# Sheet1.net
KiCad netlist of a schematic drawn in Altium Designer
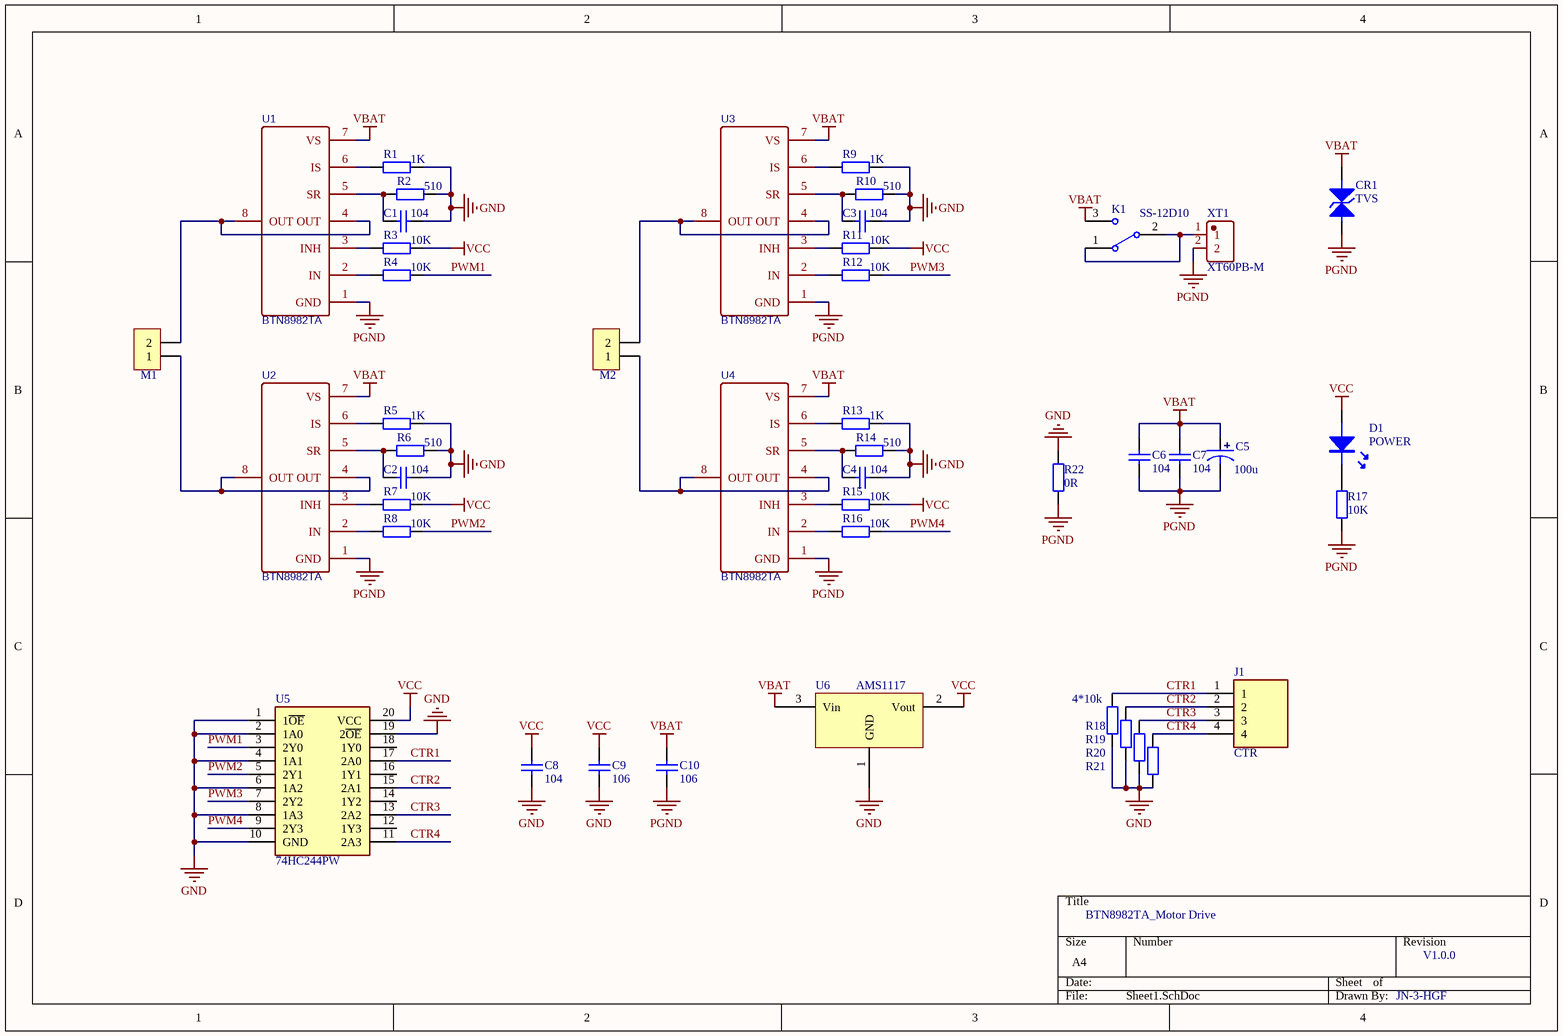
[diagram p0: Sheet1.SchDoc]

(export (version "E")
  (design (tool "Eeschema 10.0.6"))
  (components
    (comp (ref "C1")
      (value "104")
      (footprint "稽稽库:CAP0603")
      (description "Capacitor")
      (fields (field (name "Comment") "Cap") (field (name "PUBLISHER") "Altium Limited"))
      (libsource (lib "Miscellaneous Devices") (part "Cap"))
    )
    (comp (ref "C2")
      (value "104")
      (footprint "稽稽库:CAP0603")
      (description "Capacitor")
      (fields (field (name "Comment") "Cap") (field (name "PUBLISHER") "Altium Limited"))
      (libsource (lib "Miscellaneous Devices") (part "Cap"))
    )
    (comp (ref "C3")
      (value "104")
      (footprint "稽稽库:CAP0603")
      (description "Capacitor")
      (fields (field (name "Comment") "Cap") (field (name "PUBLISHER") "Altium Limited"))
      (libsource (lib "Miscellaneous Devices") (part "Cap"))
    )
    (comp (ref "C4")
      (value "104")
      (footprint "稽稽库:CAP0603")
      (description "Capacitor")
      (fields (field (name "Comment") "Cap") (field (name "PUBLISHER") "Altium Limited"))
      (libsource (lib "Miscellaneous Devices") (part "Cap"))
    )
    (comp (ref "C5")
      (value "100u")
      (footprint "SMD-EC6.3X6.3X10")
      (description "贴片电解电容")
      (libsource (lib "电容") (part "SMD_ECAP"))
    )
    (comp (ref "C6")
      (value "104")
      (footprint "稽稽库:CAP0603")
      (description "Capacitor")
      (fields (field (name "Comment") "Cap") (field (name "PUBLISHER") "Altium Limited"))
      (libsource (lib "Miscellaneous Devices") (part "Cap"))
    )
    (comp (ref "C7")
      (value "104")
      (footprint "稽稽库:CAP0603")
      (description "Capacitor")
      (fields (field (name "Comment") "Cap") (field (name "PUBLISHER") "Altium Limited"))
      (libsource (lib "Miscellaneous Devices") (part "Cap"))
    )
    (comp (ref "C8")
      (value "104")
      (footprint "稽稽库:CAP0603")
      (description "Capacitor")
      (fields (field (name "Comment") "Cap") (field (name "PUBLISHER") "Altium Limited"))
      (libsource (lib "Miscellaneous Devices") (part "Cap"))
    )
    (comp (ref "C9")
      (value "106")
      (footprint "稽稽库:CAP0603")
      (description "Capacitor")
      (fields (field (name "Comment") "Cap") (field (name "PUBLISHER") "Altium Limited"))
      (libsource (lib "Miscellaneous Devices") (part "Cap"))
    )
    (comp (ref "C10")
      (value "106")
      (footprint "稽稽库:CAP0603")
      (description "Capacitor")
      (fields (field (name "Comment") "Cap") (field (name "PUBLISHER") "Altium Limited"))
      (libsource (lib "Miscellaneous Devices") (part "Cap"))
    )
    (comp (ref "CR1")
      (value "TVS")
      (footprint "SMA/DO-214AC")
      (description "双向瞬态抑制二极管")
      (libsource (lib "二极管") (part "TVS"))
    )
    (comp (ref "D1") (value "POWER") (footprint "LED-0603G") (libsource (lib "LED") (part "LED")))
    (comp (ref "J1")
      (value "CTR")
      (footprint "XH2.54-LI-4P")
      (description "Connector")
      (fields (field (name "MANUFACTURER_PART_NUMBER") "B4B-XH-A(LF)(SN)"))
      (libsource (lib "*") (part "B4B-XH-A_LF__SN_"))
    )
    (comp (ref "K1") (value "SS-12D10") (footprint "SS-12D10") (libsource (lib "电源开关") (part "SS-12D10")))
    (comp (ref "M1")
      (value "HDR-1X2")
      (footprint "KF301-5.0-2P")
      (description "2P接插件")
      (fields (field (name "版权归属") "源创客"))
      (libsource (lib "4.10 - 接插件-脚距5.0") (part "Header 2"))
    )
    (comp (ref "M2")
      (value "HDR-1X2")
      (footprint "KF301-5.0-2P")
      (description "2P接插件")
      (fields (field (name "版权归属") "源创客"))
      (libsource (lib "4.10 - 接插件-脚距5.0") (part "Header 2"))
    )
    (comp (ref "R1")
      (value "1K")
      (footprint "稽稽库:R0603")
      (description "Resistor")
      (fields (field (name "Comment") "Res2") (field (name "PUBLISHER") "Altium Limited"))
      (libsource (lib "Miscellaneous Devices") (part "Res2"))
    )
    (comp (ref "R2")
      (value "510")
      (footprint "稽稽库:R0603")
      (description "Resistor")
      (fields (field (name "Comment") "Res2") (field (name "PUBLISHER") "Altium Limited"))
      (libsource (lib "Miscellaneous Devices") (part "Res2"))
    )
    (comp (ref "R3")
      (value "10K")
      (footprint "稽稽库:R0603")
      (description "Resistor")
      (fields (field (name "Comment") "Res2") (field (name "PUBLISHER") "Altium Limited"))
      (libsource (lib "Miscellaneous Devices") (part "Res2"))
    )
    (comp (ref "R4")
      (value "10K")
      (footprint "稽稽库:R0603")
      (description "Resistor")
      (fields (field (name "Comment") "Res2") (field (name "PUBLISHER") "Altium Limited"))
      (libsource (lib "Miscellaneous Devices") (part "Res2"))
    )
    (comp (ref "R5")
      (value "1K")
      (footprint "稽稽库:R0603")
      (description "Resistor")
      (fields (field (name "Comment") "Res2") (field (name "PUBLISHER") "Altium Limited"))
      (libsource (lib "Miscellaneous Devices") (part "Res2"))
    )
    (comp (ref "R6")
      (value "510")
      (footprint "稽稽库:R0603")
      (description "Resistor")
      (fields (field (name "Comment") "Res2") (field (name "PUBLISHER") "Altium Limited"))
      (libsource (lib "Miscellaneous Devices") (part "Res2"))
    )
    (comp (ref "R7")
      (value "10K")
      (footprint "稽稽库:R0603")
      (description "Resistor")
      (fields (field (name "Comment") "Res2") (field (name "PUBLISHER") "Altium Limited"))
      (libsource (lib "Miscellaneous Devices") (part "Res2"))
    )
    (comp (ref "R8")
      (value "10K")
      (footprint "稽稽库:R0603")
      (description "Resistor")
      (fields (field (name "Comment") "Res2") (field (name "PUBLISHER") "Altium Limited"))
      (libsource (lib "Miscellaneous Devices") (part "Res2"))
    )
    (comp (ref "R9")
      (value "1K")
      (footprint "稽稽库:R0603")
      (description "Resistor")
      (fields (field (name "Comment") "Res2") (field (name "PUBLISHER") "Altium Limited"))
      (libsource (lib "Miscellaneous Devices") (part "Res2"))
    )
    (comp (ref "R10")
      (value "510")
      (footprint "稽稽库:R0603")
      (description "Resistor")
      (fields (field (name "Comment") "Res2") (field (name "PUBLISHER") "Altium Limited"))
      (libsource (lib "Miscellaneous Devices") (part "Res2"))
    )
    (comp (ref "R11")
      (value "10K")
      (footprint "稽稽库:R0603")
      (description "Resistor")
      (fields (field (name "Comment") "Res2") (field (name "PUBLISHER") "Altium Limited"))
      (libsource (lib "Miscellaneous Devices") (part "Res2"))
    )
    (comp (ref "R12")
      (value "10K")
      (footprint "稽稽库:R0603")
      (description "Resistor")
      (fields (field (name "Comment") "Res2") (field (name "PUBLISHER") "Altium Limited"))
      (libsource (lib "Miscellaneous Devices") (part "Res2"))
    )
    (comp (ref "R13")
      (value "1K")
      (footprint "稽稽库:R0603")
      (description "Resistor")
      (fields (field (name "Comment") "Res2") (field (name "PUBLISHER") "Altium Limited"))
      (libsource (lib "Miscellaneous Devices") (part "Res2"))
    )
    (comp (ref "R14")
      (value "510")
      (footprint "稽稽库:R0603")
      (description "Resistor")
      (fields (field (name "Comment") "Res2") (field (name "PUBLISHER") "Altium Limited"))
      (libsource (lib "Miscellaneous Devices") (part "Res2"))
    )
    (comp (ref "R15")
      (value "10K")
      (footprint "稽稽库:R0603")
      (description "Resistor")
      (fields (field (name "Comment") "Res2") (field (name "PUBLISHER") "Altium Limited"))
      (libsource (lib "Miscellaneous Devices") (part "Res2"))
    )
    (comp (ref "R16")
      (value "10K")
      (footprint "稽稽库:R0603")
      (description "Resistor")
      (fields (field (name "Comment") "Res2") (field (name "PUBLISHER") "Altium Limited"))
      (libsource (lib "Miscellaneous Devices") (part "Res2"))
    )
    (comp (ref "R17")
      (value "10K")
      (footprint "稽稽库:R0603")
      (description "Resistor")
      (fields (field (name "Comment") "Res2") (field (name "PUBLISHER") "Altium Limited"))
      (libsource (lib "") (part "Res2_1"))
    )
    (comp (ref "R18")
      (value "Res2")
      (footprint "稽稽库:R0603")
      (description "Resistor")
      (fields (field (name "PUBLISHER") "Altium Limited"))
      (libsource (lib "") (part "Res2_1"))
    )
    (comp (ref "R19")
      (value "Res2")
      (footprint "稽稽库:R0603")
      (description "Resistor")
      (fields (field (name "PUBLISHER") "Altium Limited"))
      (libsource (lib "") (part "Res2_1"))
    )
    (comp (ref "R20")
      (value "Res2")
      (footprint "稽稽库:R0603")
      (description "Resistor")
      (fields (field (name "PUBLISHER") "Altium Limited"))
      (libsource (lib "") (part "Res2_1"))
    )
    (comp (ref "R21")
      (value "Res2")
      (footprint "稽稽库:R0603")
      (description "Resistor")
      (fields (field (name "PUBLISHER") "Altium Limited"))
      (libsource (lib "") (part "Res2_1"))
    )
    (comp (ref "R22")
      (value "0R")
      (footprint "R0603")
      (description "Resistor")
      (fields (field (name "Comment") "Res2") (field (name "PUBLISHER") "Altium Limited"))
      (libsource (lib "") (part "Res2_1"))
    )
    (comp (ref "U1")
      (value "BTN8982TA")
      (footprint "TO-263-7_L10.2-W10.4-P1.27-LS14.4-BR")
      (fields
        (field (name "BOM_MANUFACTURER PART") "BTN8982TAAUMA1")
        (field (name "BOM_SUPPLIER PART") "C74175")
      )
      (libsource (lib "Integrated_Library1") (part "BTN8982TA"))
    )
    (comp (ref "U2")
      (value "BTN8982TA")
      (footprint "TO-263-7_L10.2-W10.4-P1.27-LS14.4-BR")
      (fields
        (field (name "BOM_MANUFACTURER PART") "BTN8982TAAUMA1")
        (field (name "BOM_SUPPLIER PART") "C74175")
      )
      (libsource (lib "Integrated_Library1") (part "BTN8982TA"))
    )
    (comp (ref "U3")
      (value "BTN8982TA")
      (footprint "TO-263-7_L10.2-W10.4-P1.27-LS14.4-BR")
      (fields
        (field (name "BOM_MANUFACTURER PART") "BTN8982TAAUMA1")
        (field (name "BOM_SUPPLIER PART") "C74175")
      )
      (libsource (lib "Integrated_Library1") (part "BTN8982TA"))
    )
    (comp (ref "U4")
      (value "BTN8982TA")
      (footprint "TO-263-7_L10.2-W10.4-P1.27-LS14.4-BR")
      (fields
        (field (name "BOM_MANUFACTURER PART") "BTN8982TAAUMA1")
        (field (name "BOM_SUPPLIER PART") "C74175")
      )
      (libsource (lib "Integrated_Library1") (part "BTN8982TA"))
    )
    (comp (ref "U5")
      (value "74HC244PW")
      (footprint "SamacSys:SOP65P640X110-20N")
      (description "Integrated Circuit")
      (fields (field (name "MOUSER PART NUMBER") "771-74HC244PW"))
      (libsource (lib "*") (part "74HC244PW"))
    )
    (comp (ref "U6")
      (value "AMS1117")
      (footprint "SOT223_N")
      (description "三端稳压芯片")
      (libsource (lib "电源芯片") (part "AMS1117"))
    )
    (comp (ref "XT1")
      (value "XT60PB-M")
      (footprint "XT30UPB-M")
      (libsource (lib "Integrated_Library1") (part "XT60PB-M"))
    )
  )
  (nets
    (net (code "1") (name "/CTR1") (class "Default")
      (node (ref "J1") (pin "1") (pinfunction "1_1") (pintype "passive"))
      (node (ref "R18") (pin "2") (pinfunction "2_2") (pintype "passive"))
      (node (ref "U5") (pin "17") (pinfunction "2A0_17") (pintype "passive"))
    )
    (net (code "2") (name "/CTR2") (class "Default")
      (node (ref "J1") (pin "2") (pinfunction "2_2") (pintype "passive"))
      (node (ref "R19") (pin "2") (pinfunction "2_2") (pintype "passive"))
      (node (ref "U5") (pin "15") (pinfunction "2A1_15") (pintype "passive"))
    )
    (net (code "3") (name "/CTR3") (class "Default")
      (node (ref "J1") (pin "3") (pinfunction "3_3") (pintype "passive"))
      (node (ref "R20") (pin "2") (pinfunction "2_2") (pintype "passive"))
      (node (ref "U5") (pin "13") (pinfunction "2A2_13") (pintype "passive"))
    )
    (net (code "4") (name "/CTR4") (class "Default")
      (node (ref "J1") (pin "4") (pinfunction "4_4") (pintype "passive"))
      (node (ref "R21") (pin "2") (pinfunction "2_2") (pintype "passive"))
      (node (ref "U5") (pin "11") (pinfunction "2A3_11") (pintype "passive"))
    )
    (net (code "5") (name "/PWM1") (class "Default")
      (node (ref "R4") (pin "2") (pinfunction "2_2") (pintype "passive"))
      (node (ref "U5") (pin "3") (pinfunction "2Y0_3") (pintype "passive"))
    )
    (net (code "6") (name "/PWM2") (class "Default")
      (node (ref "R8") (pin "2") (pinfunction "2_2") (pintype "passive"))
      (node (ref "U5") (pin "5") (pinfunction "2Y1_5") (pintype "passive"))
    )
    (net (code "7") (name "/PWM3") (class "Default")
      (node (ref "R12") (pin "2") (pinfunction "2_2") (pintype "passive"))
      (node (ref "U5") (pin "7") (pinfunction "2Y2_7") (pintype "passive"))
    )
    (net (code "8") (name "/PWM4") (class "Default")
      (node (ref "R16") (pin "2") (pinfunction "2_2") (pintype "passive"))
      (node (ref "U5") (pin "9") (pinfunction "2Y3_9") (pintype "passive"))
    )
    (net (code "9") (name "GND") (class "Default")
      (node (ref "C1") (pin "2") (pinfunction "2_2") (pintype "passive"))
      (node (ref "C2") (pin "2") (pinfunction "2_2") (pintype "passive"))
      (node (ref "C3") (pin "2") (pinfunction "2_2") (pintype "passive"))
      (node (ref "C4") (pin "2") (pinfunction "2_2") (pintype "passive"))
      (node (ref "C8") (pin "1") (pinfunction "1_1") (pintype "passive"))
      (node (ref "C9") (pin "1") (pinfunction "1_1") (pintype "passive"))
      (node (ref "R1") (pin "2") (pinfunction "2_2") (pintype "passive"))
      (node (ref "R10") (pin "2") (pinfunction "2_2") (pintype "passive"))
      (node (ref "R13") (pin "2") (pinfunction "2_2") (pintype "passive"))
      (node (ref "R14") (pin "2") (pinfunction "2_2") (pintype "passive"))
      (node (ref "R18") (pin "1") (pinfunction "1_1") (pintype "passive"))
      (node (ref "R19") (pin "1") (pinfunction "1_1") (pintype "passive"))
      (node (ref "R2") (pin "2") (pinfunction "2_2") (pintype "passive"))
      (node (ref "R20") (pin "1") (pinfunction "1_1") (pintype "passive"))
      (node (ref "R21") (pin "1") (pinfunction "1_1") (pintype "passive"))
      (node (ref "R22") (pin "2") (pinfunction "2_2") (pintype "passive"))
      (node (ref "R5") (pin "2") (pinfunction "2_2") (pintype "passive"))
      (node (ref "R6") (pin "2") (pinfunction "2_2") (pintype "passive"))
      (node (ref "R9") (pin "2") (pinfunction "2_2") (pintype "passive"))
      (node (ref "U5") (pin "1") (pinfunction "1~{OE}_1") (pintype "passive"))
      (node (ref "U5") (pin "10") (pinfunction "GND_10") (pintype "passive"))
      (node (ref "U5") (pin "19") (pinfunction "2~{OE}_19") (pintype "passive"))
      (node (ref "U5") (pin "2") (pinfunction "1A0_2") (pintype "passive"))
      (node (ref "U5") (pin "4") (pinfunction "1A1_4") (pintype "passive"))
      (node (ref "U5") (pin "6") (pinfunction "1A2_6") (pintype "passive"))
      (node (ref "U5") (pin "8") (pinfunction "1A3_8") (pintype "passive"))
      (node (ref "U6") (pin "1") (pinfunction "GND_1") (pintype "passive"))
    )
    (net (code "10") (name "Net-(D1-PadK)") (class "Default")
      (node (ref "D1") (pin "K") (pinfunction "K_K") (pintype "passive"))
      (node (ref "R17") (pin "2") (pinfunction "2_2") (pintype "passive"))
    )
    (net (code "11") (name "Net-(K1-Pad1)") (class "Default")
      (node (ref "K1") (pin "1") (pinfunction "1_1") (pintype "passive"))
      (node (ref "K1") (pin "2") (pinfunction "2_2") (pintype "passive"))
      (node (ref "XT1") (pin "1") (pinfunction "1_1") (pintype "passive"))
    )
    (net (code "12") (name "Net-(M1-Pad1)") (class "Default")
      (node (ref "M1") (pin "1") (pinfunction "1_1") (pintype "passive"))
      (node (ref "U2") (pin "4") (pinfunction "OUT_4") (pintype "passive"))
      (node (ref "U2") (pin "8") (pinfunction "OUT_8") (pintype "passive"))
    )
    (net (code "13") (name "Net-(M1-Pad2)") (class "Default")
      (node (ref "M1") (pin "2") (pinfunction "2_2") (pintype "passive"))
      (node (ref "U1") (pin "4") (pinfunction "OUT_4") (pintype "passive"))
      (node (ref "U1") (pin "8") (pinfunction "OUT_8") (pintype "passive"))
    )
    (net (code "14") (name "Net-(M2-Pad1)") (class "Default")
      (node (ref "M2") (pin "1") (pinfunction "1_1") (pintype "passive"))
      (node (ref "U4") (pin "4") (pinfunction "OUT_4") (pintype "passive"))
      (node (ref "U4") (pin "8") (pinfunction "OUT_8") (pintype "passive"))
    )
    (net (code "15") (name "Net-(M2-Pad2)") (class "Default")
      (node (ref "M2") (pin "2") (pinfunction "2_2") (pintype "passive"))
      (node (ref "U3") (pin "4") (pinfunction "OUT_4") (pintype "passive"))
      (node (ref "U3") (pin "8") (pinfunction "OUT_8") (pintype "passive"))
    )
    (net (code "16") (name "Net-(U1-IN)") (class "Default")
      (node (ref "R4") (pin "1") (pinfunction "1_1") (pintype "passive"))
      (node (ref "U1") (pin "2") (pinfunction "IN_2") (pintype "passive"))
    )
    (net (code "17") (name "Net-(U1-INH)") (class "Default")
      (node (ref "R3") (pin "1") (pinfunction "1_1") (pintype "passive"))
      (node (ref "U1") (pin "3") (pinfunction "INH_3") (pintype "passive"))
    )
    (net (code "18") (name "Net-(U1-IS)") (class "Default")
      (node (ref "R1") (pin "1") (pinfunction "1_1") (pintype "passive"))
      (node (ref "U1") (pin "6") (pinfunction "IS_6") (pintype "passive"))
    )
    (net (code "19") (name "Net-(U1-SR)") (class "Default")
      (node (ref "C1") (pin "1") (pinfunction "1_1") (pintype "passive"))
      (node (ref "R2") (pin "1") (pinfunction "1_1") (pintype "passive"))
      (node (ref "U1") (pin "5") (pinfunction "SR_5") (pintype "passive"))
    )
    (net (code "20") (name "Net-(U2-IN)") (class "Default")
      (node (ref "R8") (pin "1") (pinfunction "1_1") (pintype "passive"))
      (node (ref "U2") (pin "2") (pinfunction "IN_2") (pintype "passive"))
    )
    (net (code "21") (name "Net-(U2-INH)") (class "Default")
      (node (ref "R7") (pin "1") (pinfunction "1_1") (pintype "passive"))
      (node (ref "U2") (pin "3") (pinfunction "INH_3") (pintype "passive"))
    )
    (net (code "22") (name "Net-(U2-IS)") (class "Default")
      (node (ref "R5") (pin "1") (pinfunction "1_1") (pintype "passive"))
      (node (ref "U2") (pin "6") (pinfunction "IS_6") (pintype "passive"))
    )
    (net (code "23") (name "Net-(U2-SR)") (class "Default")
      (node (ref "C2") (pin "1") (pinfunction "1_1") (pintype "passive"))
      (node (ref "R6") (pin "1") (pinfunction "1_1") (pintype "passive"))
      (node (ref "U2") (pin "5") (pinfunction "SR_5") (pintype "passive"))
    )
    (net (code "24") (name "Net-(U3-IN)") (class "Default")
      (node (ref "R12") (pin "1") (pinfunction "1_1") (pintype "passive"))
      (node (ref "U3") (pin "2") (pinfunction "IN_2") (pintype "passive"))
    )
    (net (code "25") (name "Net-(U3-INH)") (class "Default")
      (node (ref "R11") (pin "1") (pinfunction "1_1") (pintype "passive"))
      (node (ref "U3") (pin "3") (pinfunction "INH_3") (pintype "passive"))
    )
    (net (code "26") (name "Net-(U3-IS)") (class "Default")
      (node (ref "R9") (pin "1") (pinfunction "1_1") (pintype "passive"))
      (node (ref "U3") (pin "6") (pinfunction "IS_6") (pintype "passive"))
    )
    (net (code "27") (name "Net-(U3-SR)") (class "Default")
      (node (ref "C3") (pin "1") (pinfunction "1_1") (pintype "passive"))
      (node (ref "R10") (pin "1") (pinfunction "1_1") (pintype "passive"))
      (node (ref "U3") (pin "5") (pinfunction "SR_5") (pintype "passive"))
    )
    (net (code "28") (name "Net-(U4-IN)") (class "Default")
      (node (ref "R16") (pin "1") (pinfunction "1_1") (pintype "passive"))
      (node (ref "U4") (pin "2") (pinfunction "IN_2") (pintype "passive"))
    )
    (net (code "29") (name "Net-(U4-INH)") (class "Default")
      (node (ref "R15") (pin "1") (pinfunction "1_1") (pintype "passive"))
      (node (ref "U4") (pin "3") (pinfunction "INH_3") (pintype "passive"))
    )
    (net (code "30") (name "Net-(U4-IS)") (class "Default")
      (node (ref "R13") (pin "1") (pinfunction "1_1") (pintype "passive"))
      (node (ref "U4") (pin "6") (pinfunction "IS_6") (pintype "passive"))
    )
    (net (code "31") (name "Net-(U4-SR)") (class "Default")
      (node (ref "C4") (pin "1") (pinfunction "1_1") (pintype "passive"))
      (node (ref "R14") (pin "1") (pinfunction "1_1") (pintype "passive"))
      (node (ref "U4") (pin "5") (pinfunction "SR_5") (pintype "passive"))
    )
    (net (code "32") (name "PGND") (class "Default")
      (node (ref "C10") (pin "1") (pinfunction "1_1") (pintype "passive"))
      (node (ref "C5") (pin "2") (pinfunction "2_2") (pintype "passive"))
      (node (ref "C6") (pin "1") (pinfunction "1_1") (pintype "passive"))
      (node (ref "C7") (pin "1") (pinfunction "1_1") (pintype "passive"))
      (node (ref "CR1") (pin "A") (pinfunction "A_A") (pintype "passive"))
      (node (ref "R17") (pin "1") (pinfunction "1_1") (pintype "passive"))
      (node (ref "R22") (pin "1") (pinfunction "1_1") (pintype "passive"))
      (node (ref "U1") (pin "1") (pinfunction "GND_1") (pintype "passive"))
      (node (ref "U2") (pin "1") (pinfunction "GND_1") (pintype "passive"))
      (node (ref "U3") (pin "1") (pinfunction "GND_1") (pintype "passive"))
      (node (ref "U4") (pin "1") (pinfunction "GND_1") (pintype "passive"))
      (node (ref "XT1") (pin "2") (pinfunction "2_2") (pintype "passive"))
    )
    (net (code "33") (name "VBAT") (class "Default")
      (node (ref "C10") (pin "2") (pinfunction "2_2") (pintype "passive"))
      (node (ref "C5") (pin "1") (pinfunction "1_1") (pintype "passive"))
      (node (ref "C6") (pin "2") (pinfunction "2_2") (pintype "passive"))
      (node (ref "C7") (pin "2") (pinfunction "2_2") (pintype "passive"))
      (node (ref "CR1") (pin "K") (pinfunction "K_K") (pintype "passive"))
      (node (ref "K1") (pin "3") (pinfunction "3_3") (pintype "passive"))
      (node (ref "U1") (pin "7") (pinfunction "VS_7") (pintype "passive"))
      (node (ref "U2") (pin "7") (pinfunction "VS_7") (pintype "passive"))
      (node (ref "U3") (pin "7") (pinfunction "VS_7") (pintype "passive"))
      (node (ref "U4") (pin "7") (pinfunction "VS_7") (pintype "passive"))
      (node (ref "U6") (pin "3") (pinfunction "Vin_3") (pintype "passive"))
    )
    (net (code "34") (name "VCC") (class "Default")
      (node (ref "C8") (pin "2") (pinfunction "2_2") (pintype "passive"))
      (node (ref "C9") (pin "2") (pinfunction "2_2") (pintype "passive"))
      (node (ref "D1") (pin "A") (pinfunction "A_A") (pintype "passive"))
      (node (ref "R11") (pin "2") (pinfunction "2_2") (pintype "passive"))
      (node (ref "R15") (pin "2") (pinfunction "2_2") (pintype "passive"))
      (node (ref "R3") (pin "2") (pinfunction "2_2") (pintype "passive"))
      (node (ref "R7") (pin "2") (pinfunction "2_2") (pintype "passive"))
      (node (ref "U5") (pin "20") (pinfunction "VCC_20") (pintype "passive"))
      (node (ref "U6") (pin "2") (pinfunction "Vout_2") (pintype "passive"))
    )
    (net (code "35") (name "unconnected-(U5-1Y0-Pad18)") (class "Default")
      (node (ref "U5") (pin "18") (pinfunction "1Y0_18") (pintype "passive"))
    )
    (net (code "36") (name "unconnected-(U5-1Y1-Pad16)") (class "Default")
      (node (ref "U5") (pin "16") (pinfunction "1Y1_16") (pintype "passive"))
    )
    (net (code "37") (name "unconnected-(U5-1Y2-Pad14)") (class "Default")
      (node (ref "U5") (pin "14") (pinfunction "1Y2_14") (pintype "passive"))
    )
    (net (code "38") (name "unconnected-(U5-1Y3-Pad12)") (class "Default")
      (node (ref "U5") (pin "12") (pinfunction "1Y3_12") (pintype "passive"))
    )
  )
)
